# LED.net
KiCad netlist of a schematic drawn in Altium Designer
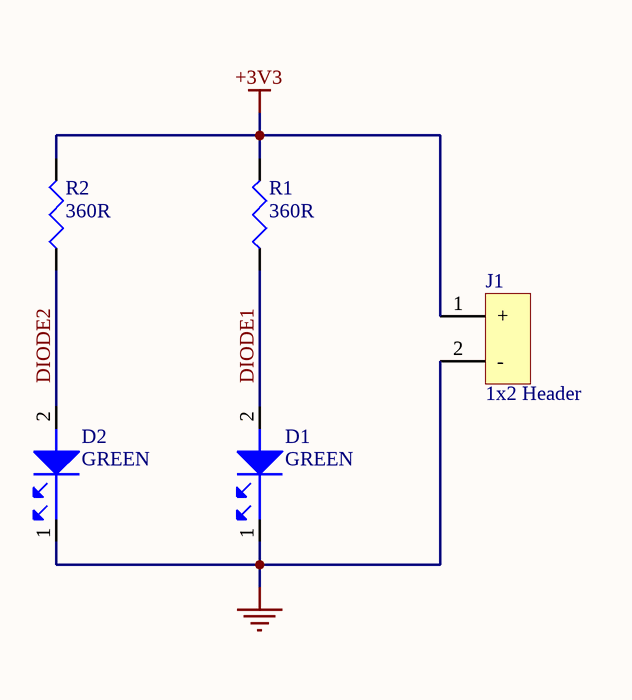
[diagram p0: LED.SchDoc]

(export (version "E")
  (design (tool "Eeschema 10.0.6"))
  (components
    (comp (ref "D1")
      (value "GREEN")
      (footprint "LED0603G")
      (description "LED GREEN ESS II SMD")
      (fields
        (field (name "MANUFACTURER") "Panasonic SSG")
        (field (name "MANUFACTURER PART NUMBER") "LNJ337W83RA")
      )
      (libsource (lib "LED_SchLib") (part "LNJ337W83RA"))
    )
    (comp (ref "D2")
      (value "GREEN")
      (footprint "LED0603G")
      (description "LED GREEN ESS II SMD")
      (fields
        (field (name "MANUFACTURER") "Panasonic SSG")
        (field (name "MANUFACTURER PART NUMBER") "LNJ337W83RA")
      )
      (libsource (lib "LED_SchLib") (part "LNJ337W83RA"))
    )
    (comp (ref "J1")
      (value "1x2 Header")
      (footprint "HD1X2")
      (description "Conn Wire to Board HDR 2 POS 2.54mm Solder ST Thru-Hole Bag")
      (fields (field (name "MANUFACTURER") "Molex") (field (name "MANUFACTURER PART NUMBER") "22-29-2021"))
      (libsource (lib "LED_SchLib") (part "22-29-2021"))
    )
    (comp (ref "R1")
      (value "360R")
      (footprint "R0805")
      (description "Res Thick Film 0805 360 Ohm 1% 0.125W(1/8W) ±100ppm/C Molded SMD Automotive Paper T/R")
      (fields
        (field (name "MANUFACTURER") "Vishay")
        (field (name "MANUFACTURER PART NUMBER") "CRCW0805360RFKEA")
      )
      (libsource (lib "LED_SchLib") (part "CRCW0805360RFKEA"))
    )
    (comp (ref "R2")
      (value "360R")
      (footprint "R0805")
      (description "Res Thick Film 0805 360 Ohm 1% 0.125W(1/8W) ±100ppm/C Molded SMD Automotive Paper T/R")
      (fields
        (field (name "MANUFACTURER") "Vishay")
        (field (name "MANUFACTURER PART NUMBER") "CRCW0805360RFKEA")
      )
      (libsource (lib "LED_SchLib") (part "CRCW0805360RFKEA"))
    )
  )
  (nets
    (net (code "1") (name "+3V3") (class "Default")
      (node (ref "J1") (pin "1") (pinfunction "+_1") (pintype "passive"))
      (node (ref "R1") (pin "2") (pinfunction "2_2") (pintype "passive"))
      (node (ref "R2") (pin "2") (pinfunction "2_2") (pintype "passive"))
    )
    (net (code "2") (name "/DIODE1") (class "Default")
      (node (ref "D1") (pin "2") (pinfunction "2_2") (pintype "passive"))
      (node (ref "R1") (pin "1") (pinfunction "1_1") (pintype "passive"))
    )
    (net (code "3") (name "/DIODE2") (class "Default")
      (node (ref "D2") (pin "2") (pinfunction "2_2") (pintype "passive"))
      (node (ref "R2") (pin "1") (pinfunction "1_1") (pintype "passive"))
    )
    (net (code "4") (name "GND") (class "Default")
      (node (ref "D1") (pin "1") (pinfunction "1_1") (pintype "passive"))
      (node (ref "D2") (pin "1") (pinfunction "1_1") (pintype "passive"))
      (node (ref "J1") (pin "2") (pinfunction "-_2") (pintype "passive"))
    )
  )
)
